# sensors-digital.net
KiCad netlist of a schematic drawn in Altium Designer
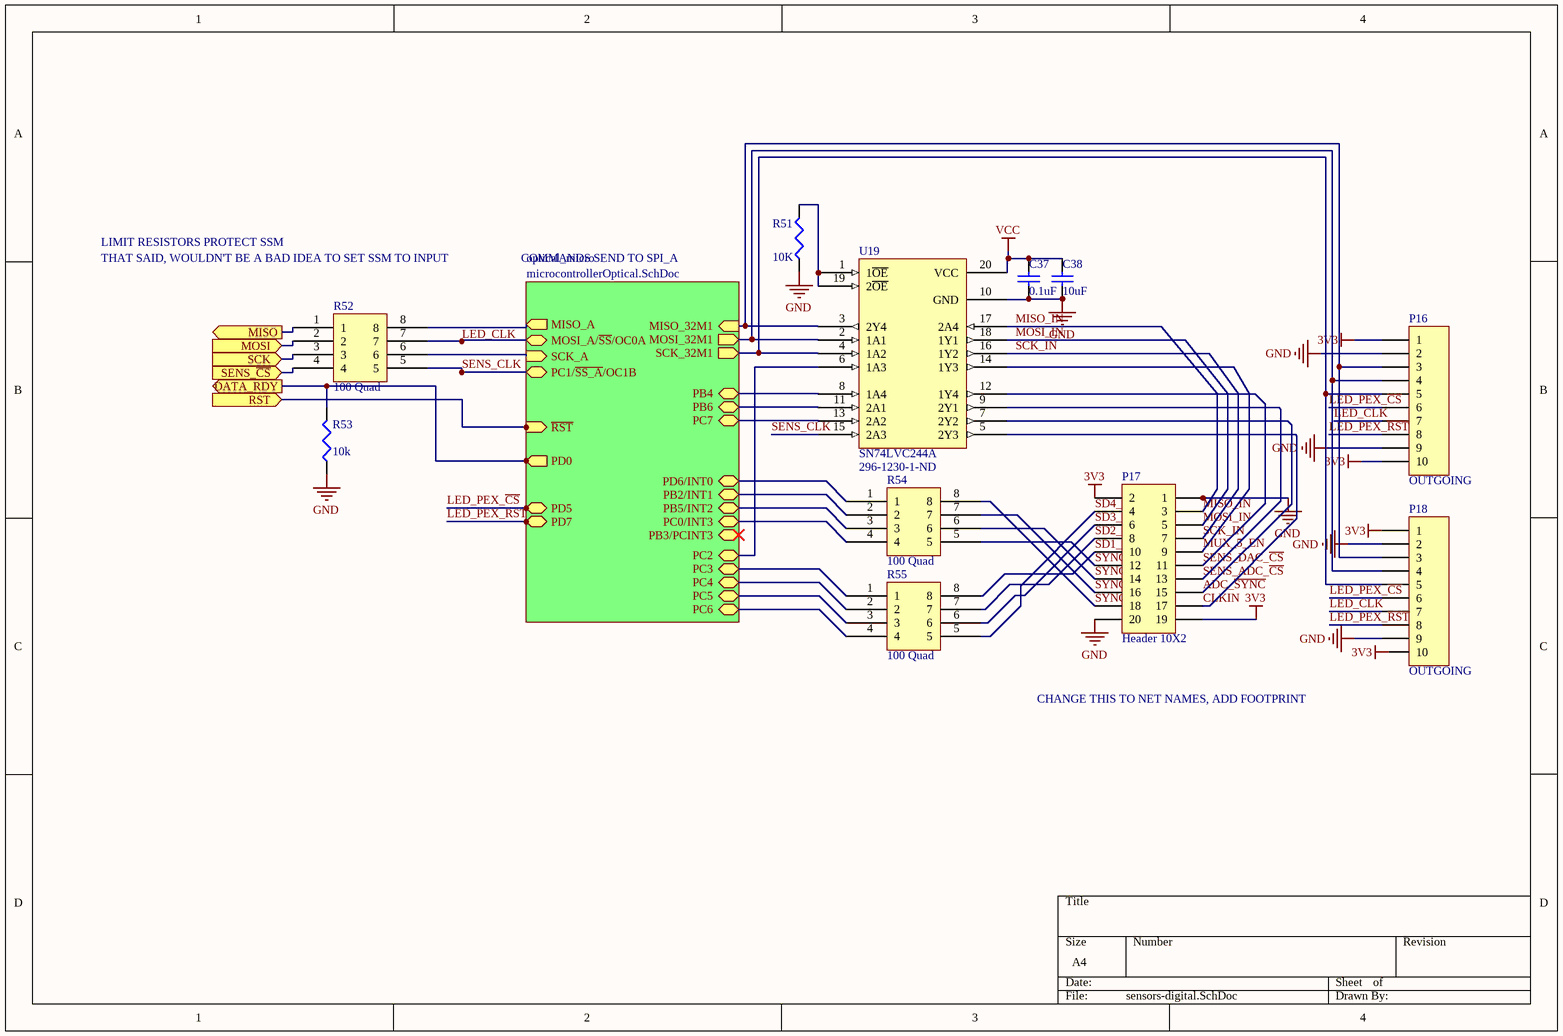
[diagram p0: sensors-digital.SchDoc]

(export (version "E")
  (design (tool "Eeschema 10.0.6"))
  (components
    (comp (ref "C37")
      (value "0.1uF")
      (footprint "1608[0603]")
      (description "Capacitor (Semiconductor SIM Model)")
      (fields (field (name "PUBLISHER") "Altium Limited"))
      (libsource (lib "Miscellaneous Devices") (part "Cap Semi"))
    )
    (comp (ref "C38")
      (value "10uF")
      (footprint "1608[0603]")
      (description "Capacitor (Semiconductor SIM Model)")
      (fields (field (name "PUBLISHER") "Altium Limited"))
      (libsource (lib "Miscellaneous Devices") (part "Cap Semi"))
    )
    (comp (ref "P16")
      (value "OUTGOING")
      (footprint "DF14-10P-1.25H(55)")
      (description "Header, 10-Pin")
      (fields (field (name "PUBLISHER") "Altium Limited"))
      (libsource (lib "Miscellaneous Connectors") (part "Header 10"))
    )
    (comp (ref "P17")
      (value "Header 10X2")
      (footprint "CON20_2X10_Female")
      (description "Header, 10-Pin, Dual row")
      (fields (field (name "PUBLISHER") "Altium Limited"))
      (libsource (lib "Miscellaneous Connectors") (part "Header 10X2"))
    )
    (comp (ref "P18")
      (value "OUTGOING")
      (footprint "DF14-10P-1.25H(55)")
      (description "Header, 10-Pin")
      (fields (field (name "PUBLISHER") "Altium Limited"))
      (libsource (lib "Miscellaneous Connectors") (part "Header 10"))
    )
    (comp (ref "R51")
      (value "10K")
      (footprint "J1-0603")
      (description "Resistor")
      (fields (field (name "PUBLISHER") "Altium Limited"))
      (libsource (lib "Miscellaneous Devices") (part "Res3"))
    )
    (comp (ref "R52")
      (value "100 Quad")
      (footprint "ResQuad-320X150")
      (description "Quad pack resistor")
      (libsource (lib "PAY") (part "Res Quad Pack"))
    )
    (comp (ref "R53")
      (value "10k")
      (footprint "J1-0603")
      (description "Resistor")
      (fields (field (name "PUBLISHER") "Altium Limited"))
      (libsource (lib "Miscellaneous Devices") (part "Res3"))
    )
    (comp (ref "R54")
      (value "100 Quad")
      (footprint "ResQuad-320X150")
      (description "Quad pack resistor")
      (libsource (lib "PAY") (part "Res Quad Pack"))
    )
    (comp (ref "R55")
      (value "100 Quad")
      (footprint "ResQuad-320X150")
      (description "Quad pack resistor")
      (libsource (lib "PAY") (part "Res Quad Pack"))
    )
    (comp (ref "U19")
      (value "SN74LVC244A")
      (footprint "SOP65P650X440-20N")
      (description "Octal buffer or driver with 3-state outputs.")
      (fields (field (name "SUPPLIER PART NUMBER 1") "296-1230-1-ND"))
      (libsource (lib "ICs") (part "SN74LVC244A"))
    )
  )
  (nets
    (net (code "1") (name "/ADC_~{SYNC}") (class "Default")
      (node (ref "P17") (pin "15") (pinfunction "15_15") (pintype "passive"))
      (node (ref "U19") (pin "7") (pinfunction "2Y2_7") (pintype "output"))
    )
    (net (code "2") (name "/CLKIN") (class "Default")
      (node (ref "P17") (pin "17") (pinfunction "17_17") (pintype "passive"))
      (node (ref "U19") (pin "5") (pinfunction "2Y3_5") (pintype "output"))
    )
    (net (code "3") (name "/DATA_RDY") (class "Default")
      (node (ref "R53") (pin "2") (pinfunction "2_2") (pintype "passive"))
    )
    (net (code "4") (name "/LED_CLK") (class "Default")
      (node (ref "P16") (pin "7") (pinfunction "7_7") (pintype "passive"))
      (node (ref "P18") (pin "7") (pinfunction "7_7") (pintype "passive"))
      (node (ref "R52") (pin "7") (pinfunction "7_7") (pintype "passive"))
    )
    (net (code "5") (name "/LED_PEX_~{CS}") (class "Default")
      (node (ref "P16") (pin "6") (pinfunction "6_6") (pintype "passive"))
      (node (ref "P18") (pin "6") (pinfunction "6_6") (pintype "passive"))
    )
    (net (code "6") (name "/LED_PEX_~{RST}") (class "Default")
      (node (ref "P16") (pin "8") (pinfunction "8_8") (pintype "passive"))
      (node (ref "P18") (pin "8") (pinfunction "8_8") (pintype "passive"))
    )
    (net (code "7") (name "/MISO") (class "Default")
      (node (ref "R52") (pin "1") (pinfunction "1_1") (pintype "passive"))
    )
    (net (code "8") (name "/MISO_32M1") (class "Default")
      (node (ref "P16") (pin "3") (pinfunction "3_3") (pintype "passive"))
      (node (ref "P18") (pin "3") (pinfunction "3_3") (pintype "passive"))
      (node (ref "U19") (pin "3") (pinfunction "2Y4_3") (pintype "output"))
    )
    (net (code "9") (name "/MISO_A") (class "Default")
      (node (ref "R52") (pin "8") (pinfunction "8_8") (pintype "passive"))
    )
    (net (code "10") (name "/MISO_IN") (class "Default")
      (node (ref "P17") (pin "3") (pinfunction "3_3") (pintype "passive"))
      (node (ref "U19") (pin "17") (pinfunction "2A4_17") (pintype "input"))
    )
    (net (code "11") (name "/MOSI") (class "Default")
      (node (ref "R52") (pin "2") (pinfunction "2_2") (pintype "passive"))
    )
    (net (code "12") (name "/MOSI_32M1") (class "Default")
      (node (ref "P16") (pin "4") (pinfunction "4_4") (pintype "passive"))
      (node (ref "P18") (pin "4") (pinfunction "4_4") (pintype "passive"))
      (node (ref "U19") (pin "2") (pinfunction "1A1_2") (pintype "input"))
    )
    (net (code "13") (name "/MOSI_IN") (class "Default")
      (node (ref "P17") (pin "5") (pinfunction "5_5") (pintype "passive"))
      (node (ref "U19") (pin "18") (pinfunction "1Y1_18") (pintype "output"))
    )
    (net (code "14") (name "/MUX_5_EN") (class "Default")
      (node (ref "P17") (pin "9") (pinfunction "9_9") (pintype "passive"))
      (node (ref "U19") (pin "14") (pinfunction "1Y3_14") (pintype "output"))
    )
    (net (code "15") (name "/PB2{slash}INT1") (class "Default")
      (node (ref "R54") (pin "2") (pinfunction "2_2") (pintype "passive"))
    )
    (net (code "17") (name "/PB4") (class "Default")
      (node (ref "U19") (pin "8") (pinfunction "1A4_8") (pintype "input"))
    )
    (net (code "18") (name "/PB5{slash}INT2") (class "Default")
      (node (ref "R54") (pin "3") (pinfunction "3_3") (pintype "passive"))
    )
    (net (code "19") (name "/PB6") (class "Default")
      (node (ref "U19") (pin "11") (pinfunction "2A1_11") (pintype "input"))
    )
    (net (code "20") (name "/PC0{slash}INT3") (class "Default")
      (node (ref "R54") (pin "4") (pinfunction "4_4") (pintype "passive"))
    )
    (net (code "21") (name "/PC2") (class "Default")
      (node (ref "U19") (pin "6") (pinfunction "1A3_6") (pintype "input"))
    )
    (net (code "22") (name "/PC3") (class "Default")
      (node (ref "R55") (pin "1") (pinfunction "1_1") (pintype "passive"))
    )
    (net (code "23") (name "/PC4") (class "Default")
      (node (ref "R55") (pin "2") (pinfunction "2_2") (pintype "passive"))
    )
    (net (code "24") (name "/PC5") (class "Default")
      (node (ref "R55") (pin "3") (pinfunction "3_3") (pintype "passive"))
    )
    (net (code "25") (name "/PC6") (class "Default")
      (node (ref "R55") (pin "4") (pinfunction "4_4") (pintype "passive"))
    )
    (net (code "26") (name "/PC7") (class "Default")
      (node (ref "U19") (pin "13") (pinfunction "2A2_13") (pintype "input"))
    )
    (net (code "27") (name "/PD6{slash}INT0") (class "Default")
      (node (ref "R54") (pin "1") (pinfunction "1_1") (pintype "passive"))
    )
    (net (code "29") (name "/SCK") (class "Default")
      (node (ref "R52") (pin "3") (pinfunction "3_3") (pintype "passive"))
    )
    (net (code "30") (name "/SCK_32M1") (class "Default")
      (node (ref "P16") (pin "5") (pinfunction "5_5") (pintype "passive"))
      (node (ref "P18") (pin "5") (pinfunction "5_5") (pintype "passive"))
      (node (ref "U19") (pin "4") (pinfunction "1A2_4") (pintype "input"))
    )
    (net (code "31") (name "/SCK_A") (class "Default")
      (node (ref "R52") (pin "6") (pinfunction "6_6") (pintype "passive"))
    )
    (net (code "32") (name "/SCK_IN") (class "Default")
      (node (ref "P17") (pin "7") (pinfunction "7_7") (pintype "passive"))
      (node (ref "U19") (pin "16") (pinfunction "1Y2_16") (pintype "output"))
    )
    (net (code "33") (name "/SD1_~{CS}") (class "Default")
      (node (ref "P17") (pin "10") (pinfunction "10_10") (pintype "passive"))
      (node (ref "R55") (pin "8") (pinfunction "8_8") (pintype "passive"))
    )
    (net (code "34") (name "/SD2_~{CS}") (class "Default")
      (node (ref "P17") (pin "8") (pinfunction "8_8") (pintype "passive"))
      (node (ref "R55") (pin "7") (pinfunction "7_7") (pintype "passive"))
    )
    (net (code "35") (name "/SD3_~{CS}") (class "Default")
      (node (ref "P17") (pin "6") (pinfunction "6_6") (pintype "passive"))
      (node (ref "R55") (pin "6") (pinfunction "6_6") (pintype "passive"))
    )
    (net (code "36") (name "/SD4_~{CS}") (class "Default")
      (node (ref "P17") (pin "4") (pinfunction "4_4") (pintype "passive"))
      (node (ref "R55") (pin "5") (pinfunction "5_5") (pintype "passive"))
    )
    (net (code "37") (name "/SENS_ADC_~{CS}") (class "Default")
      (node (ref "P17") (pin "13") (pinfunction "13_13") (pintype "passive"))
      (node (ref "U19") (pin "9") (pinfunction "2Y1_9") (pintype "output"))
    )
    (net (code "38") (name "/SENS_CLK") (class "Default")
      (node (ref "R52") (pin "5") (pinfunction "5_5") (pintype "passive"))
      (node (ref "U19") (pin "15") (pinfunction "2A3_15") (pintype "input"))
    )
    (net (code "39") (name "/SENS_DAC_~{CS}") (class "Default")
      (node (ref "P17") (pin "11") (pinfunction "11_11") (pintype "passive"))
      (node (ref "U19") (pin "12") (pinfunction "1Y4_12") (pintype "output"))
    )
    (net (code "40") (name "/SENS_~{CS}") (class "Default")
      (node (ref "R52") (pin "4") (pinfunction "4_4") (pintype "passive"))
    )
    (net (code "41") (name "/SYNCO1") (class "Default")
      (node (ref "P17") (pin "18") (pinfunction "18_18") (pintype "passive"))
      (node (ref "R54") (pin "8") (pinfunction "8_8") (pintype "passive"))
    )
    (net (code "42") (name "/SYNCO2") (class "Default")
      (node (ref "P17") (pin "16") (pinfunction "16_16") (pintype "passive"))
      (node (ref "R54") (pin "7") (pinfunction "7_7") (pintype "passive"))
    )
    (net (code "43") (name "/SYNCO3") (class "Default")
      (node (ref "P17") (pin "14") (pinfunction "14_14") (pintype "passive"))
      (node (ref "R54") (pin "6") (pinfunction "6_6") (pintype "passive"))
    )
    (net (code "44") (name "/SYNCO4") (class "Default")
      (node (ref "P17") (pin "12") (pinfunction "12_12") (pintype "passive"))
      (node (ref "R54") (pin "5") (pinfunction "5_5") (pintype "passive"))
    )
    (net (code "45") (name "3V3") (class "Default")
      (node (ref "P16") (pin "1") (pinfunction "1_1") (pintype "passive"))
      (node (ref "P16") (pin "10") (pinfunction "10_10") (pintype "passive"))
      (node (ref "P17") (pin "19") (pinfunction "19_19") (pintype "passive"))
      (node (ref "P17") (pin "2") (pinfunction "2_2") (pintype "passive"))
      (node (ref "P18") (pin "1") (pinfunction "1_1") (pintype "passive"))
    )
    (net (code "46") (name "GND") (class "Default")
      (node (ref "C37") (pin "1") (pinfunction "1_1") (pintype "passive"))
      (node (ref "C38") (pin "1") (pinfunction "1_1") (pintype "passive"))
      (node (ref "P16") (pin "2") (pinfunction "2_2") (pintype "passive"))
      (node (ref "P16") (pin "9") (pinfunction "9_9") (pintype "passive"))
      (node (ref "P17") (pin "1") (pinfunction "1_1") (pintype "passive"))
      (node (ref "P17") (pin "20") (pinfunction "20_20") (pintype "passive"))
      (node (ref "P18") (pin "2") (pinfunction "2_2") (pintype "passive"))
      (node (ref "P18") (pin "9") (pinfunction "9_9") (pintype "passive"))
      (node (ref "R51") (pin "1") (pinfunction "1_1") (pintype "passive"))
      (node (ref "R53") (pin "1") (pinfunction "1_1") (pintype "passive"))
      (node (ref "U19") (pin "10") (pinfunction "GND_10") (pintype "power_in"))
    )
    (net (code "47") (name "Net-(U19-1~{OE})") (class "Default")
      (node (ref "R51") (pin "2") (pinfunction "2_2") (pintype "passive"))
      (node (ref "U19") (pin "1") (pinfunction "1~{OE}_1") (pintype "input"))
      (node (ref "U19") (pin "19") (pinfunction "2~{OE}_19") (pintype "input"))
    )
    (net (code "48") (name "VCC") (class "Default")
      (node (ref "C37") (pin "2") (pinfunction "2_2") (pintype "passive"))
      (node (ref "C38") (pin "2") (pinfunction "2_2") (pintype "passive"))
      (node (ref "U19") (pin "20") (pinfunction "VCC_20") (pintype "power_in"))
    )
    (net (code "49") (name "unconnected-(P18-Pad10)") (class "Default")
      (node (ref "P18") (pin "10") (pinfunction "10_10") (pintype "passive"))
    )
  )
)
